# EasyEDA.net
KiCad netlist of a schematic drawn in EasyEDA
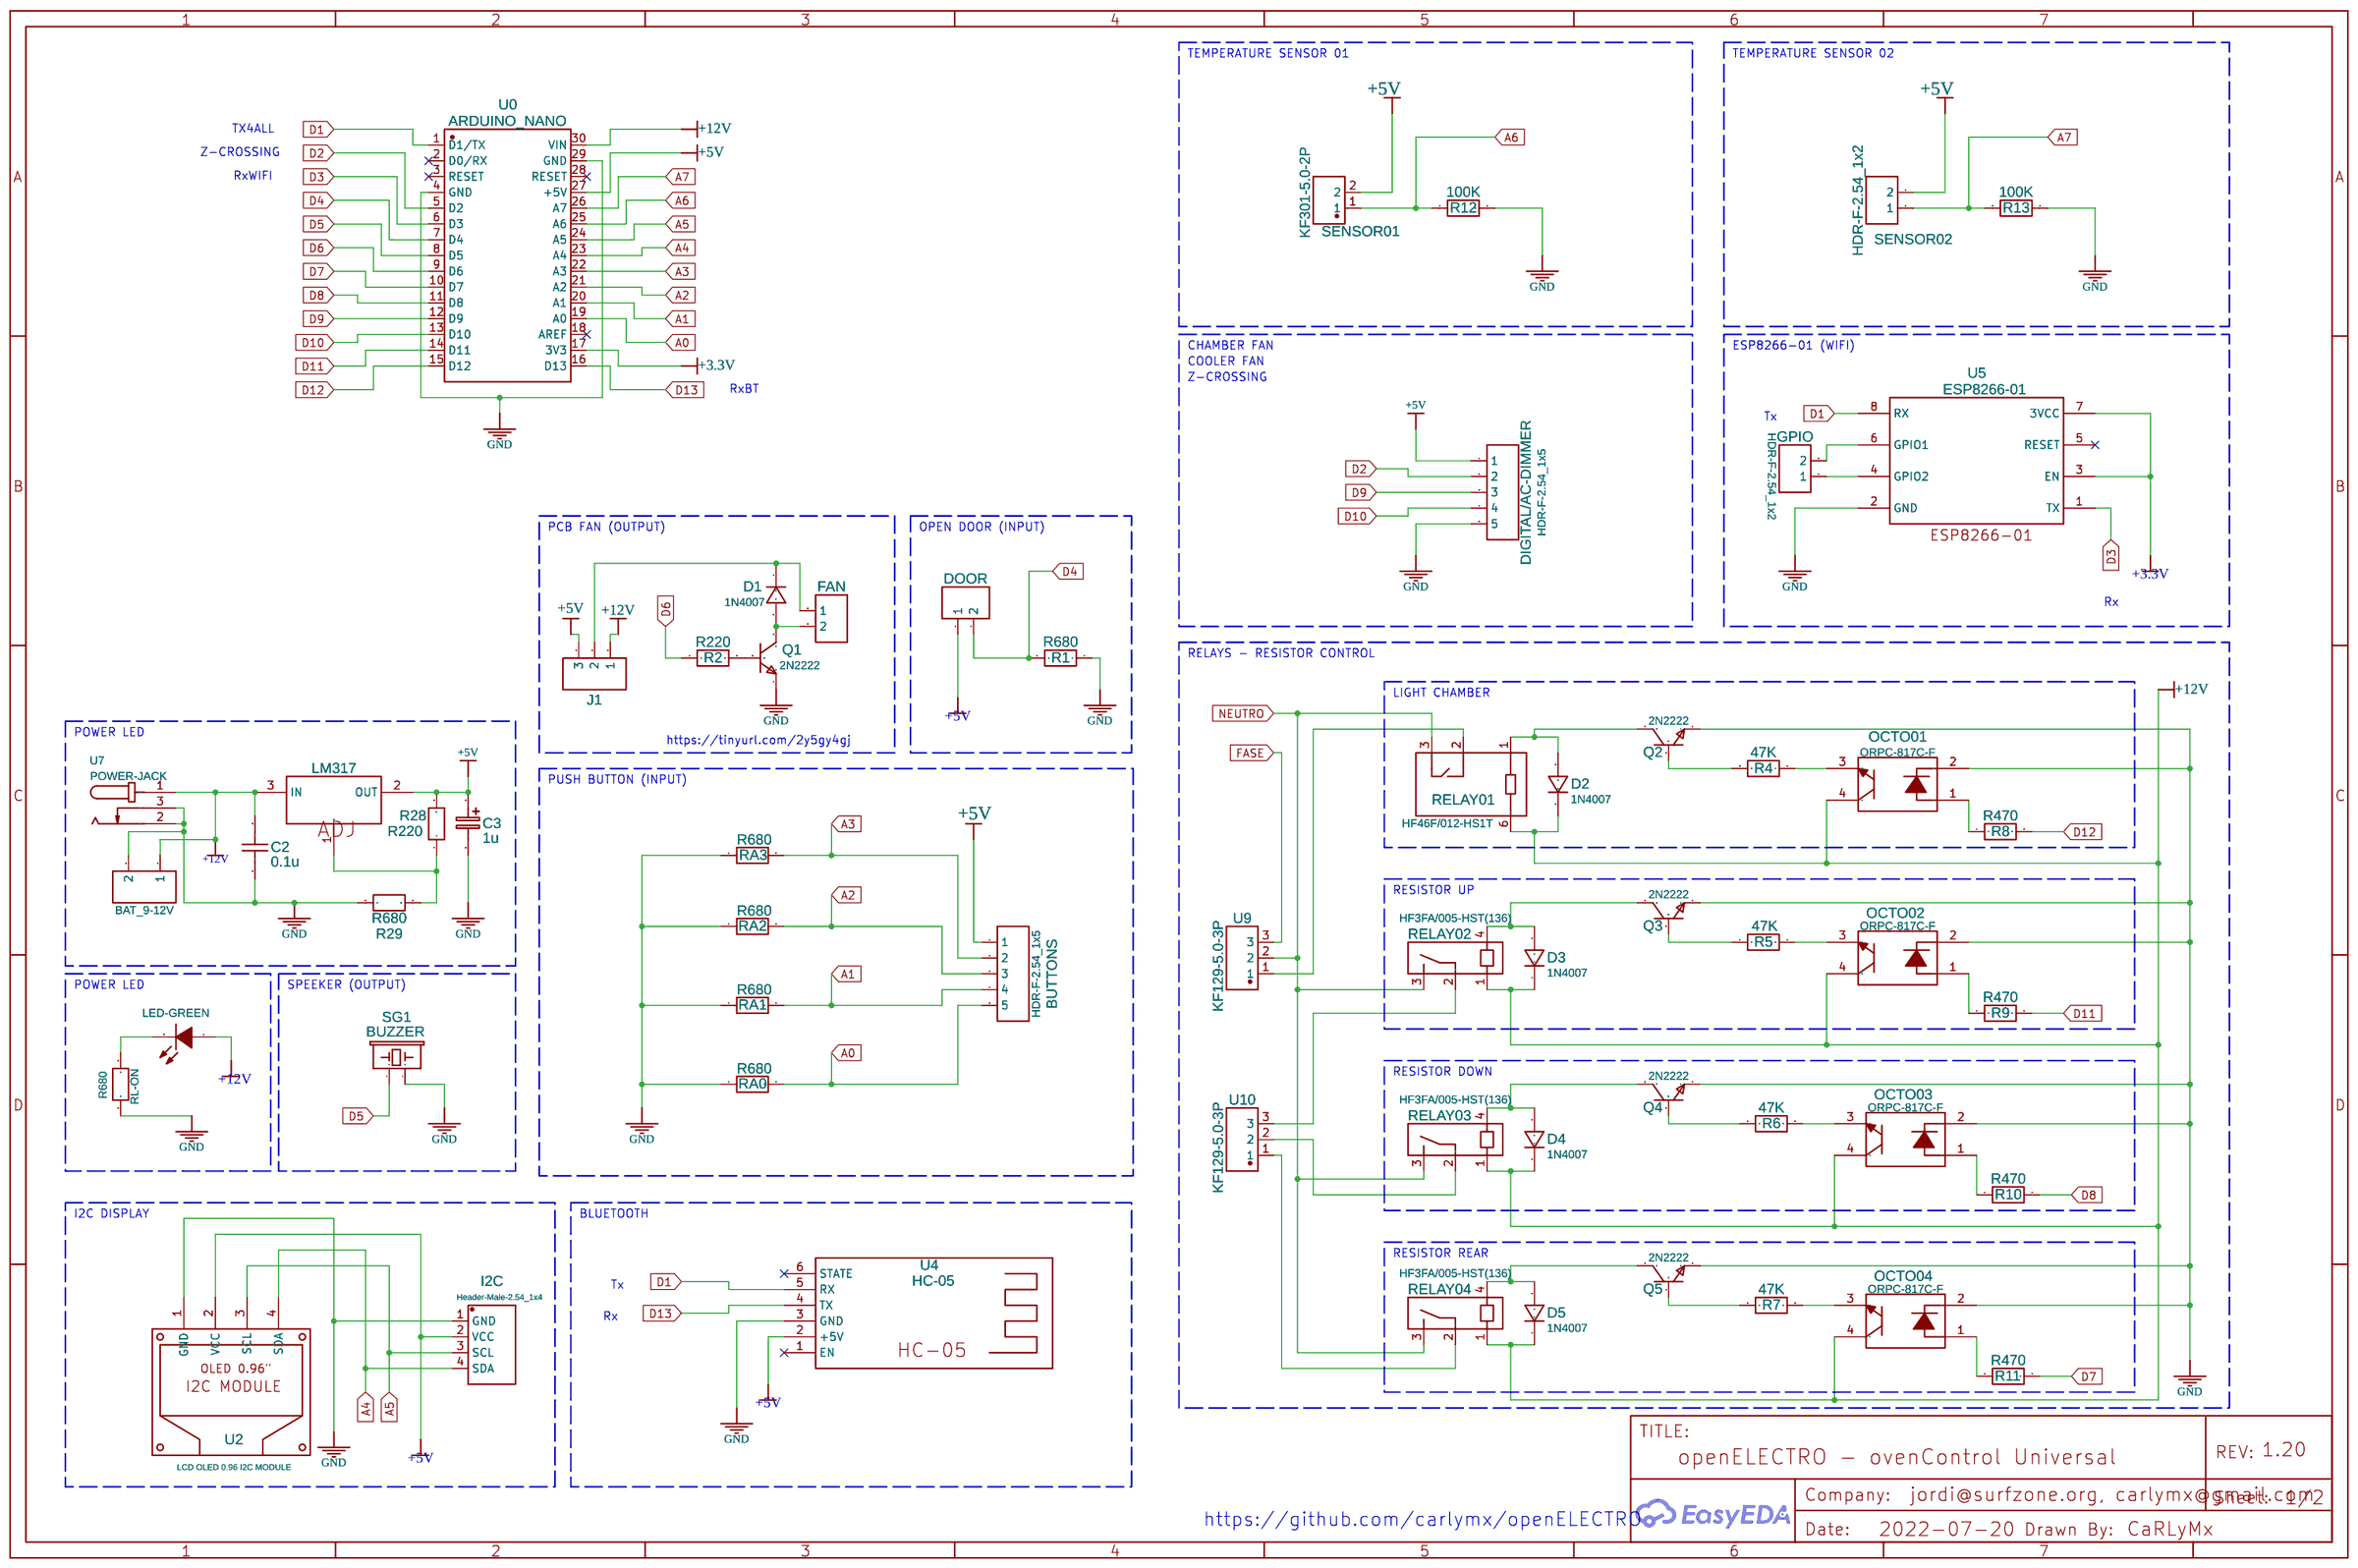
[diagram p0: openELECTRO - Universal ovenControl [v1.2] [1/2]]
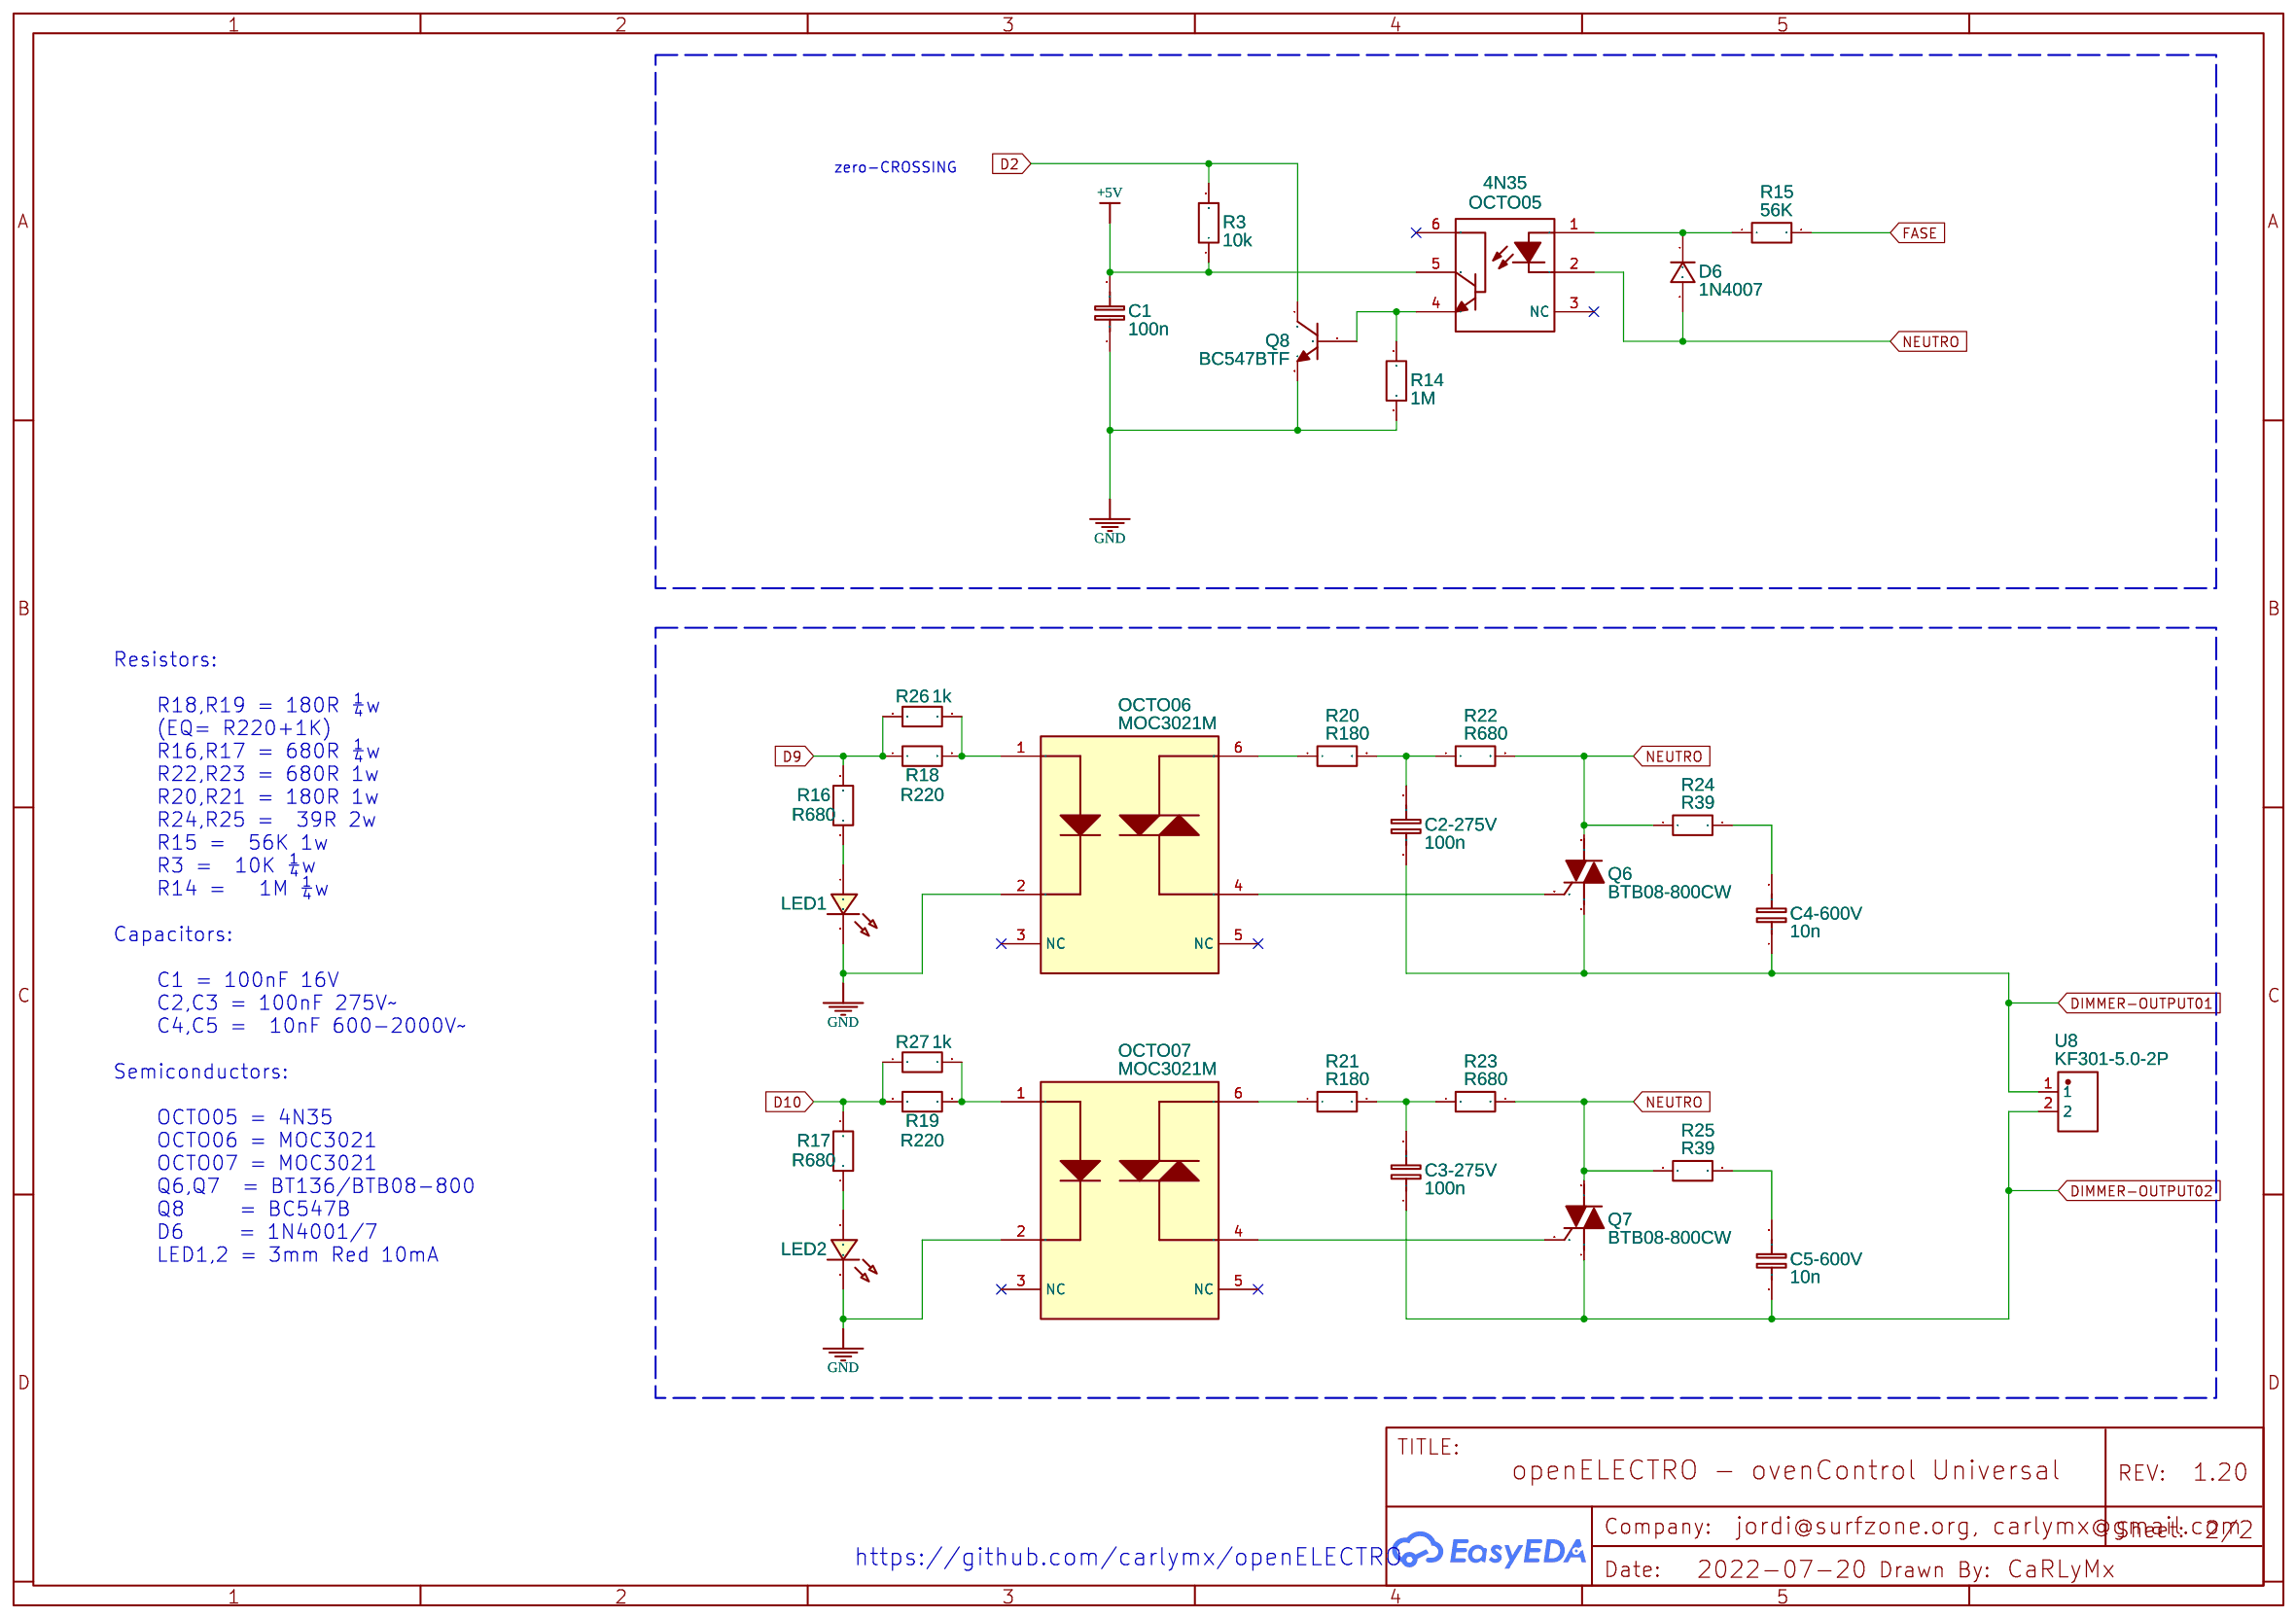
[diagram p1: openELECTRO - Universal ovenControl [v1.2] [2/2]]

(export (version "E")
  (design (tool "Eeschema 10.0.6"))
  (components
    (comp (ref "BAT_9-12V")
      (value "Header-Male-2.54_1x2")
      (fields (field (name "BOM_Manufacturer Part") "826629-2") (field (name "BOM_Supplier Part") "C86471"))
      (libsource (lib "") (part "Unknown_75_-420"))
    )
    (comp (ref "BUTTONS")
      (value "HDR-F-2.54_1x5")
      (fields (field (name "BOM_Supplier Part") "C50950"))
      (libsource (lib "") (part "HDR-F-2.54_1x5"))
    )
    (comp (ref "C2") (value "0.1u") (libsource (lib "") (part "C_0603_US")))
    (comp (ref "C3") (value "1u") (libsource (lib "") (part "C_Tan_SMD_A_EU")))
    (comp (ref "D1")
      (value "1N4007")
      (fields (field (name "BOM_Supplier Part") "C106903"))
      (libsource (lib "") (part "1N4007_1"))
    )
    (comp (ref "D2")
      (value "1N4007")
      (fields (field (name "BOM_Supplier Part") "C106903"))
      (libsource (lib "") (part "1N4007"))
    )
    (comp (ref "D3")
      (value "1N4007")
      (fields (field (name "BOM_Supplier Part") "C106903"))
      (libsource (lib "") (part "1N4007"))
    )
    (comp (ref "D4")
      (value "1N4007")
      (fields (field (name "BOM_Supplier Part") "C106903"))
      (libsource (lib "") (part "1N4007"))
    )
    (comp (ref "D5")
      (value "1N4007")
      (fields (field (name "BOM_Supplier Part") "C106903"))
      (libsource (lib "") (part "1N4007"))
    )
    (comp (ref "DIGITAL/AC-DIMMER")
      (value "HDR-F-2.54_1x5")
      (fields (field (name "BOM_Supplier Part") "C50950"))
      (libsource (lib "") (part "HDR-F-2.54_1x5_1"))
    )
    (comp (ref "DOOR")
      (value "HDR-F-2.54_1x2")
      (fields (field (name "BOM_Supplier Part") "C49661"))
      (libsource (lib "") (part "HDR-F-2.54_1x2"))
    )
    (comp (ref "FAN")
      (value "HDR-F-2.54_1x2")
      (fields (field (name "BOM_Supplier Part") "C49661"))
      (libsource (lib "") (part "HDR-F-2.54_1x2_1"))
    )
    (comp (ref "GPIO")
      (value "HDR-F-2.54_1x2")
      (fields (field (name "BOM_Supplier Part") "C49661"))
      (libsource (lib "") (part "HDR-F-2.54_1x2_3"))
    )
    (comp (ref "I2C")
      (value "Header-Male-2.54_1x4")
      (fields
        (field (name "BOM_Manufacturer Part") "210S-1*4P L=11.6MMGold-plated black")
        (field (name "BOM_Supplier Part") "C124378")
      )
      (libsource (lib "") (part "Unknown_290_-125"))
    )
    (comp (ref "J1")
      (value "HDR-F-2.54_1x3")
      (fields (field (name "BOM_Supplier Part") "C146690"))
      (libsource (lib "") (part "HDR-F-2.54_1x3"))
    )
    (comp (ref "LED-GREEN")
      (value "204-10SURD/S530-A3")
      (fields (field (name "BOM_Supplier Part") "C99772"))
      (libsource (lib "") (part "Unknown_100_-315"))
    )
    (comp (ref "LM317")
      (value "LM317LZ")
      (fields (field (name "BOM_Manufacturer Part") "LM317LZG") (field (name "BOM_Supplier Part") "C513142"))
      (libsource (lib "") (part "LM317LZG_C513142"))
    )
    (comp (ref "OCTO01")
      (value "ORPC-817C-F")
      (fields (field (name "BOM_Supplier Part") "C2842770"))
      (libsource (lib "") (part "ORPC-817C-F"))
    )
    (comp (ref "OCTO02")
      (value "ORPC-817C-F")
      (fields (field (name "BOM_Supplier Part") "C2842770"))
      (libsource (lib "") (part "ORPC-817C-F"))
    )
    (comp (ref "OCTO03")
      (value "ORPC-817C-F")
      (fields (field (name "BOM_Supplier Part") "C2842770"))
      (libsource (lib "") (part "ORPC-817C-F"))
    )
    (comp (ref "OCTO04")
      (value "ORPC-817C-F")
      (fields (field (name "BOM_Supplier Part") "C2842770"))
      (libsource (lib "") (part "ORPC-817C-F"))
    )
    (comp (ref "Q1")
      (value "2N2222")
      (fields (field (name "BOM_Supplier Part") "C118536"))
      (libsource (lib "") (part "2N2222"))
    )
    (comp (ref "Q2")
      (value "2N2222")
      (fields (field (name "BOM_Supplier Part") "C118536"))
      (libsource (lib "") (part "2N2222_1"))
    )
    (comp (ref "Q3")
      (value "2N2222")
      (fields (field (name "BOM_Supplier Part") "C118536"))
      (libsource (lib "") (part "2N2222_1"))
    )
    (comp (ref "Q4")
      (value "2N2222")
      (fields (field (name "BOM_Supplier Part") "C118536"))
      (libsource (lib "") (part "2N2222_1"))
    )
    (comp (ref "Q5")
      (value "2N2222")
      (fields (field (name "BOM_Supplier Part") "C118536"))
      (libsource (lib "") (part "2N2222_1"))
    )
    (comp (ref "R1") (value "R680") (libsource (lib "") (part "R_0603_EU_1")))
    (comp (ref "R2") (value "R220") (libsource (lib "") (part "R_0603_EU")))
    (comp (ref "R4") (value "47K") (libsource (lib "") (part "R_0603_EU_1")))
    (comp (ref "R5") (value "47K") (libsource (lib "") (part "R_0603_EU")))
    (comp (ref "R6") (value "47K") (libsource (lib "") (part "R_0603_EU")))
    (comp (ref "R7") (value "47K") (libsource (lib "") (part "R_0603_EU")))
    (comp (ref "R8") (value "R470") (libsource (lib "") (part "R_0603_EU")))
    (comp (ref "R9") (value "R470") (libsource (lib "") (part "R_0603_EU")))
    (comp (ref "R10") (value "R470") (libsource (lib "") (part "R_0603_EU")))
    (comp (ref "R11") (value "R470") (libsource (lib "") (part "R_0603_EU")))
    (comp (ref "R12") (value "100K") (libsource (lib "") (part "R_0603_EU")))
    (comp (ref "R13") (value "100K") (libsource (lib "") (part "R_0603_EU")))
    (comp (ref "R28") (value "R220") (libsource (lib "") (part "R_0603_EU_2")))
    (comp (ref "R29") (value "R680") (libsource (lib "") (part "R_0603_EU")))
    (comp (ref "RA0") (value "R680") (libsource (lib "") (part "Res_AXIAL-0.3(1/8W)_EU_1")))
    (comp (ref "RA1") (value "R680") (libsource (lib "") (part "Res_AXIAL-0.3(1/8W)_EU_1")))
    (comp (ref "RA2") (value "R680") (libsource (lib "") (part "Res_AXIAL-0.3(1/8W)_EU_1")))
    (comp (ref "RA3") (value "R680") (libsource (lib "") (part "Res_AXIAL-0.3(1/8W)_EU_1")))
    (comp (ref "RELAY01")
      (value "HF46F/012-HS1T")
      (fields (field (name "BOM_Supplier Part") "C2976852"))
      (libsource (lib "") (part "HF46F/012-HS1T"))
    )
    (comp (ref "RELAY02")
      (value "HF3FA/005-HST(136)")
      (fields (field (name "BOM_Supplier Part") "C712707"))
      (libsource (lib "") (part "HF3FA/005-HST(136)"))
    )
    (comp (ref "RELAY03")
      (value "HF3FA/005-HST(136)")
      (fields (field (name "BOM_Supplier Part") "C712707"))
      (libsource (lib "") (part "HF3FA/005-HST(136)"))
    )
    (comp (ref "RELAY04")
      (value "HF3FA/005-HST(136)")
      (fields (field (name "BOM_Supplier Part") "C712707"))
      (libsource (lib "") (part "HF3FA/005-HST(136)"))
    )
    (comp (ref "RL-ON") (value "R680") (libsource (lib "") (part "Res_AXIAL-0.3(1/8W)_EU")))
    (comp (ref "SENSOR01")
      (value "KF301-5.0-2P")
      (fields (field (name "BOM_Supplier Part") "C474881"))
      (libsource (lib "") (part "KF301-5.0-2P"))
    )
    (comp (ref "SENSOR02")
      (value "HDR-F-2.54_1x2")
      (fields (field (name "BOM_Supplier Part") "C49661"))
      (libsource (lib "") (part "HDR-F-2.54_1x2_2"))
    )
    (comp (ref "SG1") (value "BUZZER") (libsource (lib "") (part "Unknown_235_-300")))
    (comp (ref "U0")
      (value "ARDUINO_NANO")
      (fields (field (name "BOM_Supplier Part") "C9900017879"))
      (libsource (lib "") (part "ARDUINO_NANO"))
    )
    (comp (ref "U2")
      (value "LCD OLED 0.96 I2C MODULE")
      (fields (field (name "BOM_Manufacturer Part") "Control Chip SSD1306"))
      (libsource (lib "") (part "Unknown_80_-135"))
    )
    (comp (ref "U4") (value "HC-05") (libsource (lib "") (part "Unknown_500_-180")))
    (comp (ref "U5") (value "ESP8266-01") (libsource (lib "") (part "ESP8266-01")))
    (comp (ref "U7")
      (value "POWER-JACK")
      (fields (field (name "BOM_Supplier Part") "C9900001795"))
      (libsource (lib "") (part "POWER-JACK"))
    )
    (comp (ref "U9")
      (value "KF129-5.0-3P")
      (fields (field (name "BOM_Supplier Part") "C475091"))
      (libsource (lib "") (part "KF129-5.0-3P"))
    )
    (comp (ref "U10")
      (value "KF129-5.0-3P")
      (fields (field (name "BOM_Supplier Part") "C475091"))
      (libsource (lib "") (part "KF129-5.0-3P"))
    )
    (comp (ref "C1") (value "100n") (libsource (lib "") (part "C_0603_EU")))
    (comp (ref "C2-275V") (value "100n") (libsource (lib "") (part "C_0603_EU_2")))
    (comp (ref "C3-275V") (value "100n") (libsource (lib "") (part "C_0603_EU_4")))
    (comp (ref "C4-600V") (value "10n") (libsource (lib "") (part "C_0603_EU_3")))
    (comp (ref "C5-600V") (value "10n") (libsource (lib "") (part "C_0603_EU_1")))
    (comp (ref "D6")
      (value "1N4007")
      (fields (field (name "BOM_Supplier Part") "C106903"))
      (libsource (lib "") (part "1N4007"))
    )
    (comp (ref "LED1")
      (value "LED-TH-3mm_R")
      (fields
        (field (name "BOM_Manufacturer Part") "204-10SDRD/S530-A3-L")
        (field (name "BOM_Supplier Part") "C84774")
      )
      (libsource (lib "") (part "LED-TH-3mm_R"))
    )
    (comp (ref "LED2")
      (value "LED-TH-3mm_R")
      (fields
        (field (name "BOM_Manufacturer Part") "204-10SDRD/S530-A3-L")
        (field (name "BOM_Supplier Part") "C84774")
      )
      (libsource (lib "") (part "LED-TH-3mm_R"))
    )
    (comp (ref "OCTO05")
      (value "4N35")
      (fields (field (name "BOM_Supplier Part") "C57084"))
      (libsource (lib "") (part "4N35"))
    )
    (comp (ref "OCTO06")
      (value "MOC3021M")
      (fields (field (name "BOM_Supplier Part") "C5242"))
      (libsource (lib "") (part "MOC3021M"))
    )
    (comp (ref "OCTO07")
      (value "MOC3021M")
      (fields (field (name "BOM_Supplier Part") "C5242"))
      (libsource (lib "") (part "MOC3021M"))
    )
    (comp (ref "Q6")
      (value "BTB08-800CW")
      (fields (field (name "BOM_Supplier Part") "C2900905"))
      (libsource (lib "") (part "BTB08-800CW"))
    )
    (comp (ref "Q7")
      (value "BTB08-800CW")
      (fields (field (name "BOM_Supplier Part") "C2900905"))
      (libsource (lib "") (part "BTB08-800CW"))
    )
    (comp (ref "Q8")
      (value "BC547BTF")
      (fields (field (name "BOM_Supplier Part") "C900798"))
      (libsource (lib "") (part "BC547BTF"))
    )
    (comp (ref "R3") (value "10k") (libsource (lib "") (part "R_AXIAL-0.3_EU")))
    (comp (ref "R14") (value "1M") (libsource (lib "") (part "R_AXIAL-0.3_EU")))
    (comp (ref "R15") (value "56K") (libsource (lib "") (part "R_AXIAL-0.3_EU_1")))
    (comp (ref "R16") (value "R680") (libsource (lib "") (part "R_AXIAL-0.3_EU")))
    (comp (ref "R17") (value "R680") (libsource (lib "") (part "R_AXIAL-0.3_EU")))
    (comp (ref "R18") (value "R220") (libsource (lib "") (part "R_AXIAL-0.3_EU_1")))
    (comp (ref "R19") (value "R220") (libsource (lib "") (part "R_AXIAL-0.3_EU_1")))
    (comp (ref "R20") (value "R180") (libsource (lib "") (part "R_AXIAL-0.3_EU_1")))
    (comp (ref "R21") (value "R180") (libsource (lib "") (part "R_AXIAL-0.3_EU_1")))
    (comp (ref "R22") (value "R680") (libsource (lib "") (part "R_AXIAL-0.3_EU_1")))
    (comp (ref "R23") (value "R680") (libsource (lib "") (part "R_AXIAL-0.3_EU_1")))
    (comp (ref "R24") (value "R39") (libsource (lib "") (part "R_AXIAL-0.3_EU_1")))
    (comp (ref "R25") (value "R39") (libsource (lib "") (part "R_AXIAL-0.3_EU_1")))
    (comp (ref "R26") (value "1k") (libsource (lib "") (part "R_0603_EU")))
    (comp (ref "R27") (value "1k") (libsource (lib "") (part "R_0603_EU")))
    (comp (ref "U8")
      (value "KF301-5.0-2P")
      (fields (field (name "BOM_Supplier Part") "C474881"))
      (libsource (lib "") (part "KF301-5.0-2P"))
    )
  )
  (nets
    (net (code "1") (name "+3.3V") (class "Default")
      (node (ref "U0") (pin "17") (pinfunction "3V3_17") (pintype "unspecified"))
      (node (ref "U5") (pin "3") (pinfunction "EN_3") (pintype "unspecified"))
      (node (ref "U5") (pin "7") (pinfunction "3VCC_7") (pintype "unspecified"))
    )
    (net (code "2") (name "+5V") (class "Default")
      (node (ref "BUTTONS") (pin "1") (pinfunction "1_1") (pintype "unspecified"))
      (node (ref "C1") (pin "2") (pinfunction "2_2") (pintype "unspecified"))
      (node (ref "C3") (pin "1") (pinfunction "1_1") (pintype "unspecified"))
      (node (ref "DIGITAL/AC-DIMMER") (pin "1") (pinfunction "1_1") (pintype "unspecified"))
      (node (ref "DOOR") (pin "1") (pinfunction "1_1") (pintype "input"))
      (node (ref "I2C") (pin "2") (pinfunction "VCC_2") (pintype "unspecified"))
      (node (ref "J1") (pin "3") (pinfunction "3_3") (pintype "input"))
      (node (ref "LM317") (pin "2") (pinfunction "OUT_2") (pintype "passive"))
      (node (ref "OCTO05") (pin "5") (pinfunction "5_5") (pintype "unspecified"))
      (node (ref "R28") (pin "2") (pinfunction "2_2") (pintype "unspecified"))
      (node (ref "R3") (pin "1") (pinfunction "1_1") (pintype "unspecified"))
      (node (ref "SENSOR01") (pin "2") (pinfunction "2_2") (pintype "unspecified"))
      (node (ref "SENSOR02") (pin "2") (pinfunction "2_2") (pintype "input"))
      (node (ref "U0") (pin "27") (pinfunction "+5V_27") (pintype "unspecified"))
      (node (ref "U2") (pin "2") (pinfunction "VCC_2") (pintype "unspecified"))
      (node (ref "U4") (pin "2") (pinfunction "+5V_2") (pintype "unspecified"))
    )
    (net (code "3") (name "+12V") (class "Default")
      (node (ref "BAT_9-12V") (pin "1") (pinfunction "1_1") (pintype "unspecified"))
      (node (ref "C2") (pin "2") (pinfunction "2_2") (pintype "unspecified"))
      (node (ref "D2") (pin "1") (pinfunction "1_1") (pintype "unspecified"))
      (node (ref "D3") (pin "1") (pinfunction "1_1") (pintype "unspecified"))
      (node (ref "D4") (pin "1") (pinfunction "1_1") (pintype "unspecified"))
      (node (ref "D5") (pin "1") (pinfunction "1_1") (pintype "unspecified"))
      (node (ref "J1") (pin "1") (pinfunction "1_1") (pintype "input"))
      (node (ref "LED-GREEN") (pin "1") (pinfunction "A_1") (pintype "unspecified"))
      (node (ref "LM317") (pin "3") (pinfunction "IN_3") (pintype "passive"))
      (node (ref "OCTO01") (pin "4") (pinfunction "4_4") (pintype "unspecified"))
      (node (ref "OCTO02") (pin "4") (pinfunction "4_4") (pintype "unspecified"))
      (node (ref "OCTO03") (pin "4") (pinfunction "4_4") (pintype "unspecified"))
      (node (ref "OCTO04") (pin "4") (pinfunction "4_4") (pintype "unspecified"))
      (node (ref "RELAY01") (pin "6") (pinfunction "6_6") (pintype "unspecified"))
      (node (ref "RELAY02") (pin "1") (pinfunction "1_1") (pintype "unspecified"))
      (node (ref "RELAY03") (pin "1") (pinfunction "1_1") (pintype "unspecified"))
      (node (ref "RELAY04") (pin "1") (pinfunction "1_1") (pintype "unspecified"))
      (node (ref "U0") (pin "30") (pinfunction "VIN_30") (pintype "unspecified"))
      (node (ref "U7") (pin "1") (pinfunction "1_1") (pintype "unspecified"))
    )
    (net (code "4") (name "A0") (class "Default")
      (node (ref "BUTTONS") (pin "5") (pinfunction "5_5") (pintype "unspecified"))
      (node (ref "RA0") (pin "2") (pinfunction "2_2") (pintype "unspecified"))
      (node (ref "U0") (pin "19") (pinfunction "A0_19") (pintype "unspecified"))
    )
    (net (code "5") (name "A1") (class "Default")
      (node (ref "BUTTONS") (pin "4") (pinfunction "4_4") (pintype "unspecified"))
      (node (ref "RA1") (pin "2") (pinfunction "2_2") (pintype "unspecified"))
      (node (ref "U0") (pin "20") (pinfunction "A1_20") (pintype "unspecified"))
    )
    (net (code "6") (name "A2") (class "Default")
      (node (ref "BUTTONS") (pin "3") (pinfunction "3_3") (pintype "unspecified"))
      (node (ref "RA2") (pin "2") (pinfunction "2_2") (pintype "unspecified"))
      (node (ref "U0") (pin "21") (pinfunction "A2_21") (pintype "unspecified"))
    )
    (net (code "7") (name "A3") (class "Default")
      (node (ref "BUTTONS") (pin "2") (pinfunction "2_2") (pintype "unspecified"))
      (node (ref "RA3") (pin "2") (pinfunction "2_2") (pintype "unspecified"))
      (node (ref "U0") (pin "22") (pinfunction "A3_22") (pintype "unspecified"))
    )
    (net (code "8") (name "A4") (class "Default")
      (node (ref "I2C") (pin "4") (pinfunction "SDA_4") (pintype "unspecified"))
      (node (ref "U0") (pin "23") (pinfunction "A4_23") (pintype "unspecified"))
      (node (ref "U2") (pin "4") (pinfunction "SDA_4") (pintype "unspecified"))
    )
    (net (code "9") (name "A5") (class "Default")
      (node (ref "I2C") (pin "3") (pinfunction "SCL_3") (pintype "unspecified"))
      (node (ref "U0") (pin "24") (pinfunction "A5_24") (pintype "unspecified"))
      (node (ref "U2") (pin "3") (pinfunction "SCL_3") (pintype "unspecified"))
    )
    (net (code "10") (name "A6") (class "Default")
      (node (ref "R12") (pin "1") (pinfunction "1_1") (pintype "unspecified"))
      (node (ref "SENSOR01") (pin "1") (pinfunction "1_1") (pintype "unspecified"))
      (node (ref "U0") (pin "25") (pinfunction "A6_25") (pintype "unspecified"))
    )
    (net (code "11") (name "A7") (class "Default")
      (node (ref "R13") (pin "1") (pinfunction "1_1") (pintype "unspecified"))
      (node (ref "SENSOR02") (pin "1") (pinfunction "1_1") (pintype "input"))
      (node (ref "U0") (pin "26") (pinfunction "A7_26") (pintype "unspecified"))
    )
    (net (code "12") (name "D1") (class "Default")
      (node (ref "U0") (pin "1") (pinfunction "D1/TX_1") (pintype "unspecified"))
      (node (ref "U4") (pin "5") (pinfunction "RX_5") (pintype "unspecified"))
      (node (ref "U5") (pin "8") (pinfunction "RX_8") (pintype "unspecified"))
    )
    (net (code "13") (name "D2") (class "Default")
      (node (ref "DIGITAL/AC-DIMMER") (pin "2") (pinfunction "2_2") (pintype "unspecified"))
      (node (ref "Q8") (pin "1") (pinfunction "C_1") (pintype "unspecified"))
      (node (ref "R3") (pin "2") (pinfunction "2_2") (pintype "unspecified"))
      (node (ref "U0") (pin "5") (pinfunction "D2_5") (pintype "unspecified"))
    )
    (net (code "14") (name "D3") (class "Default")
      (node (ref "U0") (pin "6") (pinfunction "D3_6") (pintype "unspecified"))
      (node (ref "U5") (pin "1") (pinfunction "TX_1") (pintype "unspecified"))
    )
    (net (code "15") (name "D4") (class "Default")
      (node (ref "DOOR") (pin "2") (pinfunction "2_2") (pintype "input"))
      (node (ref "R1") (pin "2") (pinfunction "2_2") (pintype "unspecified"))
      (node (ref "U0") (pin "7") (pinfunction "D4_7") (pintype "unspecified"))
    )
    (net (code "16") (name "D5") (class "Default")
      (node (ref "SG1") (pin "+") (pinfunction "1_+") (pintype "unspecified"))
      (node (ref "U0") (pin "8") (pinfunction "D5_8") (pintype "unspecified"))
    )
    (net (code "17") (name "D6") (class "Default")
      (node (ref "R2") (pin "1") (pinfunction "1_1") (pintype "unspecified"))
      (node (ref "U0") (pin "9") (pinfunction "D6_9") (pintype "unspecified"))
    )
    (net (code "18") (name "D7") (class "Default")
      (node (ref "R11") (pin "2") (pinfunction "2_2") (pintype "unspecified"))
      (node (ref "U0") (pin "10") (pinfunction "D7_10") (pintype "unspecified"))
    )
    (net (code "19") (name "D8") (class "Default")
      (node (ref "R10") (pin "2") (pinfunction "2_2") (pintype "unspecified"))
      (node (ref "U0") (pin "11") (pinfunction "D8_11") (pintype "unspecified"))
    )
    (net (code "20") (name "D9") (class "Default")
      (node (ref "DIGITAL/AC-DIMMER") (pin "3") (pinfunction "3_3") (pintype "unspecified"))
      (node (ref "R16") (pin "2") (pinfunction "2_2") (pintype "unspecified"))
      (node (ref "R18") (pin "1") (pinfunction "1_1") (pintype "unspecified"))
      (node (ref "R26") (pin "1") (pinfunction "1_1") (pintype "unspecified"))
      (node (ref "U0") (pin "12") (pinfunction "D9_12") (pintype "unspecified"))
    )
    (net (code "21") (name "D10") (class "Default")
      (node (ref "DIGITAL/AC-DIMMER") (pin "4") (pinfunction "4_4") (pintype "unspecified"))
      (node (ref "R17") (pin "2") (pinfunction "2_2") (pintype "unspecified"))
      (node (ref "R19") (pin "1") (pinfunction "1_1") (pintype "unspecified"))
      (node (ref "R27") (pin "1") (pinfunction "1_1") (pintype "unspecified"))
      (node (ref "U0") (pin "13") (pinfunction "D10_13") (pintype "unspecified"))
    )
    (net (code "22") (name "D11") (class "Default")
      (node (ref "R9") (pin "2") (pinfunction "2_2") (pintype "unspecified"))
      (node (ref "U0") (pin "14") (pinfunction "D11_14") (pintype "unspecified"))
    )
    (net (code "23") (name "D12") (class "Default")
      (node (ref "R8") (pin "2") (pinfunction "2_2") (pintype "unspecified"))
      (node (ref "U0") (pin "15") (pinfunction "D12_15") (pintype "unspecified"))
    )
    (net (code "24") (name "D13") (class "Default")
      (node (ref "U0") (pin "16") (pinfunction "D13_16") (pintype "unspecified"))
      (node (ref "U4") (pin "4") (pinfunction "TX_4") (pintype "unspecified"))
    )
    (net (code "25") (name "DIMMER-OUTPUT01") (class "Default")
      (node (ref "C2-275V") (pin "1") (pinfunction "1_1") (pintype "unspecified"))
      (node (ref "C4-600V") (pin "1") (pinfunction "1_1") (pintype "unspecified"))
      (node (ref "Q6") (pin "1") (pinfunction "T1_1") (pintype "unspecified"))
      (node (ref "U8") (pin "1") (pinfunction "1_1") (pintype "unspecified"))
    )
    (net (code "26") (name "DIMMER-OUTPUT02") (class "Default")
      (node (ref "C3-275V") (pin "1") (pinfunction "1_1") (pintype "unspecified"))
      (node (ref "C5-600V") (pin "1") (pinfunction "1_1") (pintype "unspecified"))
      (node (ref "Q7") (pin "1") (pinfunction "T1_1") (pintype "unspecified"))
      (node (ref "U8") (pin "2") (pinfunction "2_2") (pintype "unspecified"))
    )
    (net (code "27") (name "FASE") (class "Default")
      (node (ref "R15") (pin "2") (pinfunction "2_2") (pintype "unspecified"))
      (node (ref "U9") (pin "3") (pinfunction "3_3") (pintype "unspecified"))
    )
    (net (code "28") (name "GND") (class "Default")
      (node (ref "BAT_9-12V") (pin "2") (pinfunction "2_2") (pintype "unspecified"))
      (node (ref "C1") (pin "1") (pinfunction "1_1") (pintype "unspecified"))
      (node (ref "C2") (pin "1") (pinfunction "1_1") (pintype "unspecified"))
      (node (ref "C3") (pin "2") (pinfunction "2_2") (pintype "unspecified"))
      (node (ref "DIGITAL/AC-DIMMER") (pin "5") (pinfunction "5_5") (pintype "unspecified"))
      (node (ref "I2C") (pin "1") (pinfunction "GND_1") (pintype "unspecified"))
      (node (ref "LED1") (pin "2") (pinfunction "2_2") (pintype "unspecified"))
      (node (ref "LED2") (pin "2") (pinfunction "2_2") (pintype "unspecified"))
      (node (ref "OCTO01") (pin "2") (pinfunction "2_2") (pintype "unspecified"))
      (node (ref "OCTO02") (pin "2") (pinfunction "2_2") (pintype "unspecified"))
      (node (ref "OCTO03") (pin "2") (pinfunction "2_2") (pintype "unspecified"))
      (node (ref "OCTO04") (pin "2") (pinfunction "2_2") (pintype "unspecified"))
      (node (ref "OCTO06") (pin "2") (pinfunction "2_2") (pintype "input"))
      (node (ref "OCTO07") (pin "2") (pinfunction "2_2") (pintype "input"))
      (node (ref "Q1") (pin "1") (pinfunction "E_1") (pintype "unspecified"))
      (node (ref "Q2") (pin "1") (pinfunction "E_1") (pintype "unspecified"))
      (node (ref "Q3") (pin "1") (pinfunction "E_1") (pintype "unspecified"))
      (node (ref "Q4") (pin "1") (pinfunction "E_1") (pintype "unspecified"))
      (node (ref "Q5") (pin "1") (pinfunction "E_1") (pintype "unspecified"))
      (node (ref "Q8") (pin "3") (pinfunction "E_3") (pintype "unspecified"))
      (node (ref "R1") (pin "1") (pinfunction "1_1") (pintype "unspecified"))
      (node (ref "R12") (pin "2") (pinfunction "2_2") (pintype "unspecified"))
      (node (ref "R13") (pin "2") (pinfunction "2_2") (pintype "unspecified"))
      (node (ref "R14") (pin "1") (pinfunction "1_1") (pintype "unspecified"))
      (node (ref "R29") (pin "1") (pinfunction "1_1") (pintype "unspecified"))
      (node (ref "RA0") (pin "1") (pinfunction "1_1") (pintype "unspecified"))
      (node (ref "RA1") (pin "1") (pinfunction "1_1") (pintype "unspecified"))
      (node (ref "RA2") (pin "1") (pinfunction "1_1") (pintype "unspecified"))
      (node (ref "RA3") (pin "1") (pinfunction "1_1") (pintype "unspecified"))
      (node (ref "RL-ON") (pin "1") (pinfunction "1_1") (pintype "unspecified"))
      (node (ref "SG1") (pin "-") (pinfunction "2_-") (pintype "unspecified"))
      (node (ref "U0") (pin "29") (pinfunction "GND_29") (pintype "unspecified"))
      (node (ref "U0") (pin "4") (pinfunction "GND_4") (pintype "unspecified"))
      (node (ref "U2") (pin "1") (pinfunction "GND_1") (pintype "unspecified"))
      (node (ref "U4") (pin "3") (pinfunction "GND_3") (pintype "unspecified"))
      (node (ref "U5") (pin "2") (pinfunction "GND_2") (pintype "unspecified"))
      (node (ref "U7") (pin "2") (pinfunction "2_2") (pintype "unspecified"))
      (node (ref "U7") (pin "3") (pinfunction "3_3") (pintype "unspecified"))
    )
    (net (code "29") (name "NEUTRO") (class "Default")
      (node (ref "D6") (pin "2") (pinfunction "2_2") (pintype "unspecified"))
      (node (ref "OCTO05") (pin "2") (pinfunction "2_2") (pintype "unspecified"))
      (node (ref "Q6") (pin "2") (pinfunction "T2_2") (pintype "unspecified"))
      (node (ref "Q7") (pin "2") (pinfunction "T2_2") (pintype "unspecified"))
      (node (ref "R22") (pin "2") (pinfunction "2_2") (pintype "unspecified"))
      (node (ref "R23") (pin "2") (pinfunction "2_2") (pintype "unspecified"))
      (node (ref "R24") (pin "1") (pinfunction "1_1") (pintype "unspecified"))
      (node (ref "R25") (pin "1") (pinfunction "1_1") (pintype "unspecified"))
      (node (ref "RELAY01") (pin "3") (pinfunction "3_3") (pintype "unspecified"))
      (node (ref "RELAY02") (pin "3") (pinfunction "3_3") (pintype "unspecified"))
      (node (ref "RELAY03") (pin "3") (pinfunction "3_3") (pintype "unspecified"))
      (node (ref "RELAY04") (pin "3") (pinfunction "3_3") (pintype "unspecified"))
      (node (ref "U9") (pin "2") (pinfunction "2_2") (pintype "unspecified"))
    )
    (net (code "30") (name "Net-(C2-275V-Pad2)") (class "Default")
      (node (ref "C2-275V") (pin "2") (pinfunction "2_2") (pintype "unspecified"))
      (node (ref "R20") (pin "2") (pinfunction "2_2") (pintype "unspecified"))
      (node (ref "R22") (pin "1") (pinfunction "1_1") (pintype "unspecified"))
    )
    (net (code "31") (name "Net-(C3-275V-Pad2)") (class "Default")
      (node (ref "C3-275V") (pin "2") (pinfunction "2_2") (pintype "unspecified"))
      (node (ref "R21") (pin "2") (pinfunction "2_2") (pintype "unspecified"))
      (node (ref "R23") (pin "1") (pinfunction "1_1") (pintype "unspecified"))
    )
    (net (code "32") (name "Net-(C4-600V-Pad2)") (class "Default")
      (node (ref "C4-600V") (pin "2") (pinfunction "2_2") (pintype "unspecified"))
      (node (ref "R24") (pin "2") (pinfunction "2_2") (pintype "unspecified"))
    )
    (net (code "33") (name "Net-(C5-600V-Pad2)") (class "Default")
      (node (ref "C5-600V") (pin "2") (pinfunction "2_2") (pintype "unspecified"))
      (node (ref "R25") (pin "2") (pinfunction "2_2") (pintype "unspecified"))
    )
    (net (code "34") (name "Net-(D1-Pad1)") (class "Default")
      (node (ref "D1") (pin "1") (pinfunction "1_1") (pintype "unspecified"))
      (node (ref "FAN") (pin "1") (pinfunction "1_1") (pintype "input"))
      (node (ref "J1") (pin "2") (pinfunction "2_2") (pintype "input"))
    )
    (net (code "35") (name "Net-(D6-Pad1)") (class "Default")
      (node (ref "D6") (pin "1") (pinfunction "1_1") (pintype "unspecified"))
      (node (ref "OCTO05") (pin "1") (pinfunction "1_1") (pintype "unspecified"))
      (node (ref "R15") (pin "1") (pinfunction "1_1") (pintype "unspecified"))
    )
    (net (code "36") (name "Net-(LED-GREEN-K)") (class "Default")
      (node (ref "LED-GREEN") (pin "2") (pinfunction "K_2") (pintype "unspecified"))
      (node (ref "RL-ON") (pin "2") (pinfunction "2_2") (pintype "unspecified"))
    )
    (net (code "37") (name "Net-(LED1-Pad1)") (class "Default")
      (node (ref "LED1") (pin "1") (pinfunction "1_1") (pintype "unspecified"))
      (node (ref "R16") (pin "1") (pinfunction "1_1") (pintype "unspecified"))
    )
    (net (code "38") (name "Net-(LED2-Pad1)") (class "Default")
      (node (ref "LED2") (pin "1") (pinfunction "1_1") (pintype "unspecified"))
      (node (ref "R17") (pin "1") (pinfunction "1_1") (pintype "unspecified"))
    )
    (net (code "39") (name "Net-(LM317-ADJ)") (class "Default")
      (node (ref "LM317") (pin "1") (pinfunction "ADJ_1") (pintype "passive"))
      (node (ref "R28") (pin "1") (pinfunction "1_1") (pintype "unspecified"))
      (node (ref "R29") (pin "2") (pinfunction "2_2") (pintype "unspecified"))
    )
    (net (code "40") (name "Net-(OCTO01-Pad1)") (class "Default")
      (node (ref "OCTO01") (pin "1") (pinfunction "1_1") (pintype "unspecified"))
      (node (ref "R8") (pin "1") (pinfunction "1_1") (pintype "unspecified"))
    )
    (net (code "41") (name "Net-(OCTO01-Pad3)") (class "Default")
      (node (ref "OCTO01") (pin "3") (pinfunction "3_3") (pintype "unspecified"))
      (node (ref "R4") (pin "1") (pinfunction "1_1") (pintype "unspecified"))
    )
    (net (code "42") (name "Net-(OCTO02-Pad1)") (class "Default")
      (node (ref "OCTO02") (pin "1") (pinfunction "1_1") (pintype "unspecified"))
      (node (ref "R9") (pin "1") (pinfunction "1_1") (pintype "unspecified"))
    )
    (net (code "43") (name "Net-(OCTO02-Pad3)") (class "Default")
      (node (ref "OCTO02") (pin "3") (pinfunction "3_3") (pintype "unspecified"))
      (node (ref "R5") (pin "2") (pinfunction "2_2") (pintype "unspecified"))
    )
    (net (code "44") (name "Net-(OCTO03-Pad1)") (class "Default")
      (node (ref "OCTO03") (pin "1") (pinfunction "1_1") (pintype "unspecified"))
      (node (ref "R10") (pin "1") (pinfunction "1_1") (pintype "unspecified"))
    )
    (net (code "45") (name "Net-(OCTO03-Pad3)") (class "Default")
      (node (ref "OCTO03") (pin "3") (pinfunction "3_3") (pintype "unspecified"))
      (node (ref "R6") (pin "2") (pinfunction "2_2") (pintype "unspecified"))
    )
    (net (code "46") (name "Net-(OCTO04-Pad1)") (class "Default")
      (node (ref "OCTO04") (pin "1") (pinfunction "1_1") (pintype "unspecified"))
      (node (ref "R11") (pin "1") (pinfunction "1_1") (pintype "unspecified"))
    )
    (net (code "47") (name "Net-(OCTO04-Pad3)") (class "Default")
      (node (ref "OCTO04") (pin "3") (pinfunction "3_3") (pintype "unspecified"))
      (node (ref "R7") (pin "2") (pinfunction "2_2") (pintype "unspecified"))
    )
    (net (code "48") (name "Net-(OCTO06-Pad1)") (class "Default")
      (node (ref "OCTO06") (pin "1") (pinfunction "1_1") (pintype "input"))
      (node (ref "R18") (pin "2") (pinfunction "2_2") (pintype "unspecified"))
      (node (ref "R26") (pin "2") (pinfunction "2_2") (pintype "unspecified"))
    )
    (net (code "49") (name "Net-(OCTO06-Pad6)") (class "Default")
      (node (ref "OCTO06") (pin "6") (pinfunction "6_6") (pintype "input"))
      (node (ref "R20") (pin "1") (pinfunction "1_1") (pintype "unspecified"))
    )
    (net (code "50") (name "Net-(OCTO07-Pad1)") (class "Default")
      (node (ref "OCTO07") (pin "1") (pinfunction "1_1") (pintype "input"))
      (node (ref "R19") (pin "2") (pinfunction "2_2") (pintype "unspecified"))
      (node (ref "R27") (pin "2") (pinfunction "2_2") (pintype "unspecified"))
    )
    (net (code "51") (name "Net-(OCTO07-Pad6)") (class "Default")
      (node (ref "OCTO07") (pin "6") (pinfunction "6_6") (pintype "input"))
      (node (ref "R21") (pin "1") (pinfunction "1_1") (pintype "unspecified"))
    )
    (net (code "52") (name "Net-(Q1-B)") (class "Default")
      (node (ref "Q1") (pin "2") (pinfunction "B_2") (pintype "unspecified"))
      (node (ref "R2") (pin "2") (pinfunction "2_2") (pintype "unspecified"))
    )
    (net (code "53") (name "Net-(Q1-C)") (class "Default")
      (node (ref "D1") (pin "2") (pinfunction "2_2") (pintype "unspecified"))
      (node (ref "FAN") (pin "2") (pinfunction "2_2") (pintype "input"))
      (node (ref "Q1") (pin "3") (pinfunction "C_3") (pintype "unspecified"))
    )
    (net (code "54") (name "Net-(Q2-B)") (class "Default")
      (node (ref "Q2") (pin "2") (pinfunction "B_2") (pintype "unspecified"))
      (node (ref "R4") (pin "2") (pinfunction "2_2") (pintype "unspecified"))
    )
    (net (code "55") (name "Net-(Q2-C)") (class "Default")
      (node (ref "D2") (pin "2") (pinfunction "2_2") (pintype "unspecified"))
      (node (ref "Q2") (pin "3") (pinfunction "C_3") (pintype "unspecified"))
      (node (ref "RELAY01") (pin "1") (pinfunction "1_1") (pintype "unspecified"))
    )
    (net (code "56") (name "Net-(Q3-B)") (class "Default")
      (node (ref "Q3") (pin "2") (pinfunction "B_2") (pintype "unspecified"))
      (node (ref "R5") (pin "1") (pinfunction "1_1") (pintype "unspecified"))
    )
    (net (code "57") (name "Net-(Q3-C)") (class "Default")
      (node (ref "D3") (pin "2") (pinfunction "2_2") (pintype "unspecified"))
      (node (ref "Q3") (pin "3") (pinfunction "C_3") (pintype "unspecified"))
      (node (ref "RELAY02") (pin "4") (pinfunction "4_4") (pintype "unspecified"))
    )
    (net (code "58") (name "Net-(Q4-B)") (class "Default")
      (node (ref "Q4") (pin "2") (pinfunction "B_2") (pintype "unspecified"))
      (node (ref "R6") (pin "1") (pinfunction "1_1") (pintype "unspecified"))
    )
    (net (code "59") (name "Net-(Q4-C)") (class "Default")
      (node (ref "D4") (pin "2") (pinfunction "2_2") (pintype "unspecified"))
      (node (ref "Q4") (pin "3") (pinfunction "C_3") (pintype "unspecified"))
      (node (ref "RELAY03") (pin "4") (pinfunction "4_4") (pintype "unspecified"))
    )
    (net (code "60") (name "Net-(Q5-B)") (class "Default")
      (node (ref "Q5") (pin "2") (pinfunction "B_2") (pintype "unspecified"))
      (node (ref "R7") (pin "1") (pinfunction "1_1") (pintype "unspecified"))
    )
    (net (code "61") (name "Net-(Q5-C)") (class "Default")
      (node (ref "D5") (pin "2") (pinfunction "2_2") (pintype "unspecified"))
      (node (ref "Q5") (pin "3") (pinfunction "C_3") (pintype "unspecified"))
      (node (ref "RELAY04") (pin "4") (pinfunction "4_4") (pintype "unspecified"))
    )
    (net (code "62") (name "Net-(Q6-G)") (class "Default")
      (node (ref "OCTO06") (pin "4") (pinfunction "4_4") (pintype "input"))
      (node (ref "Q6") (pin "3") (pinfunction "G_3") (pintype "unspecified"))
    )
    (net (code "63") (name "Net-(Q7-G)") (class "Default")
      (node (ref "OCTO07") (pin "4") (pinfunction "4_4") (pintype "input"))
      (node (ref "Q7") (pin "3") (pinfunction "G_3") (pintype "unspecified"))
    )
    (net (code "64") (name "Net-(Q8-B)") (class "Default")
      (node (ref "OCTO05") (pin "4") (pinfunction "4_4") (pintype "unspecified"))
      (node (ref "Q8") (pin "2") (pinfunction "B_2") (pintype "unspecified"))
      (node (ref "R14") (pin "2") (pinfunction "2_2") (pintype "unspecified"))
    )
    (net (code "65") (name "Net-(RELAY01-Pad2)") (class "Default")
      (node (ref "RELAY01") (pin "2") (pinfunction "2_2") (pintype "unspecified"))
      (node (ref "U9") (pin "1") (pinfunction "1_1") (pintype "unspecified"))
    )
    (net (code "66") (name "Net-(RELAY02-Pad2)") (class "Default")
      (node (ref "RELAY02") (pin "2") (pinfunction "2_2") (pintype "unspecified"))
      (node (ref "U10") (pin "3") (pinfunction "3_3") (pintype "unspecified"))
    )
    (net (code "67") (name "Net-(RELAY03-Pad2)") (class "Default")
      (node (ref "RELAY03") (pin "2") (pinfunction "2_2") (pintype "unspecified"))
      (node (ref "U10") (pin "2") (pinfunction "2_2") (pintype "unspecified"))
    )
    (net (code "68") (name "Net-(RELAY04-Pad2)") (class "Default")
      (node (ref "RELAY04") (pin "2") (pinfunction "2_2") (pintype "unspecified"))
      (node (ref "U10") (pin "1") (pinfunction "1_1") (pintype "unspecified"))
    )
    (net (code "69") (name "Net-(U5-GPIO1)") (class "Default")
      (node (ref "GPIO") (pin "2") (pinfunction "2_2") (pintype "input"))
      (node (ref "U5") (pin "6") (pinfunction "GPIO1_6") (pintype "unspecified"))
    )
    (net (code "70") (name "Net-(U5-GPIO2)") (class "Default")
      (node (ref "GPIO") (pin "1") (pinfunction "1_1") (pintype "input"))
      (node (ref "U5") (pin "4") (pinfunction "GPIO2_4") (pintype "unspecified"))
    )
    (net (code "71") (name "unconnected-(OCTO05-NC-Pad3)") (class "Default")
      (node (ref "OCTO05") (pin "3") (pinfunction "NC_3") (pintype "unspecified+no_connect"))
    )
    (net (code "72") (name "unconnected-(OCTO05-Pad6)") (class "Default")
      (node (ref "OCTO05") (pin "6") (pinfunction "6_6") (pintype "unspecified+no_connect"))
    )
    (net (code "73") (name "unconnected-(OCTO06-NC-Pad3)") (class "Default")
      (node (ref "OCTO06") (pin "3") (pinfunction "NC_3") (pintype "unspecified+no_connect"))
    )
    (net (code "74") (name "unconnected-(OCTO06-NC-Pad5)") (class "Default")
      (node (ref "OCTO06") (pin "5") (pinfunction "NC_5") (pintype "unspecified+no_connect"))
    )
    (net (code "75") (name "unconnected-(OCTO07-NC-Pad3)") (class "Default")
      (node (ref "OCTO07") (pin "3") (pinfunction "NC_3") (pintype "unspecified+no_connect"))
    )
    (net (code "76") (name "unconnected-(OCTO07-NC-Pad5)") (class "Default")
      (node (ref "OCTO07") (pin "5") (pinfunction "NC_5") (pintype "unspecified+no_connect"))
    )
    (net (code "77") (name "unconnected-(U0-AREF-Pad18)") (class "Default")
      (node (ref "U0") (pin "18") (pinfunction "AREF_18") (pintype "unspecified+no_connect"))
    )
    (net (code "78") (name "unconnected-(U0-D0{slash}RX-Pad2)") (class "Default")
      (node (ref "U0") (pin "2") (pinfunction "D0/RX_2") (pintype "unspecified+no_connect"))
    )
    (net (code "79") (name "unconnected-(U0-RESET-Pad3)") (class "Default")
      (node (ref "U0") (pin "3") (pinfunction "RESET_3") (pintype "unspecified+no_connect"))
    )
    (net (code "80") (name "unconnected-(U0-RESET-Pad28)") (class "Default")
      (node (ref "U0") (pin "28") (pinfunction "RESET_28") (pintype "unspecified+no_connect"))
    )
    (net (code "81") (name "unconnected-(U4-EN-Pad1)") (class "Default")
      (node (ref "U4") (pin "1") (pinfunction "EN_1") (pintype "unspecified+no_connect"))
    )
    (net (code "82") (name "unconnected-(U4-STATE-Pad6)") (class "Default")
      (node (ref "U4") (pin "6") (pinfunction "STATE_6") (pintype "unspecified+no_connect"))
    )
    (net (code "83") (name "unconnected-(U5-RESET-Pad5)") (class "Default")
      (node (ref "U5") (pin "5") (pinfunction "RESET_5") (pintype "unspecified+no_connect"))
    )
  )
)
